# M111A.net
KiCad netlist of a schematic drawn in EAGLE
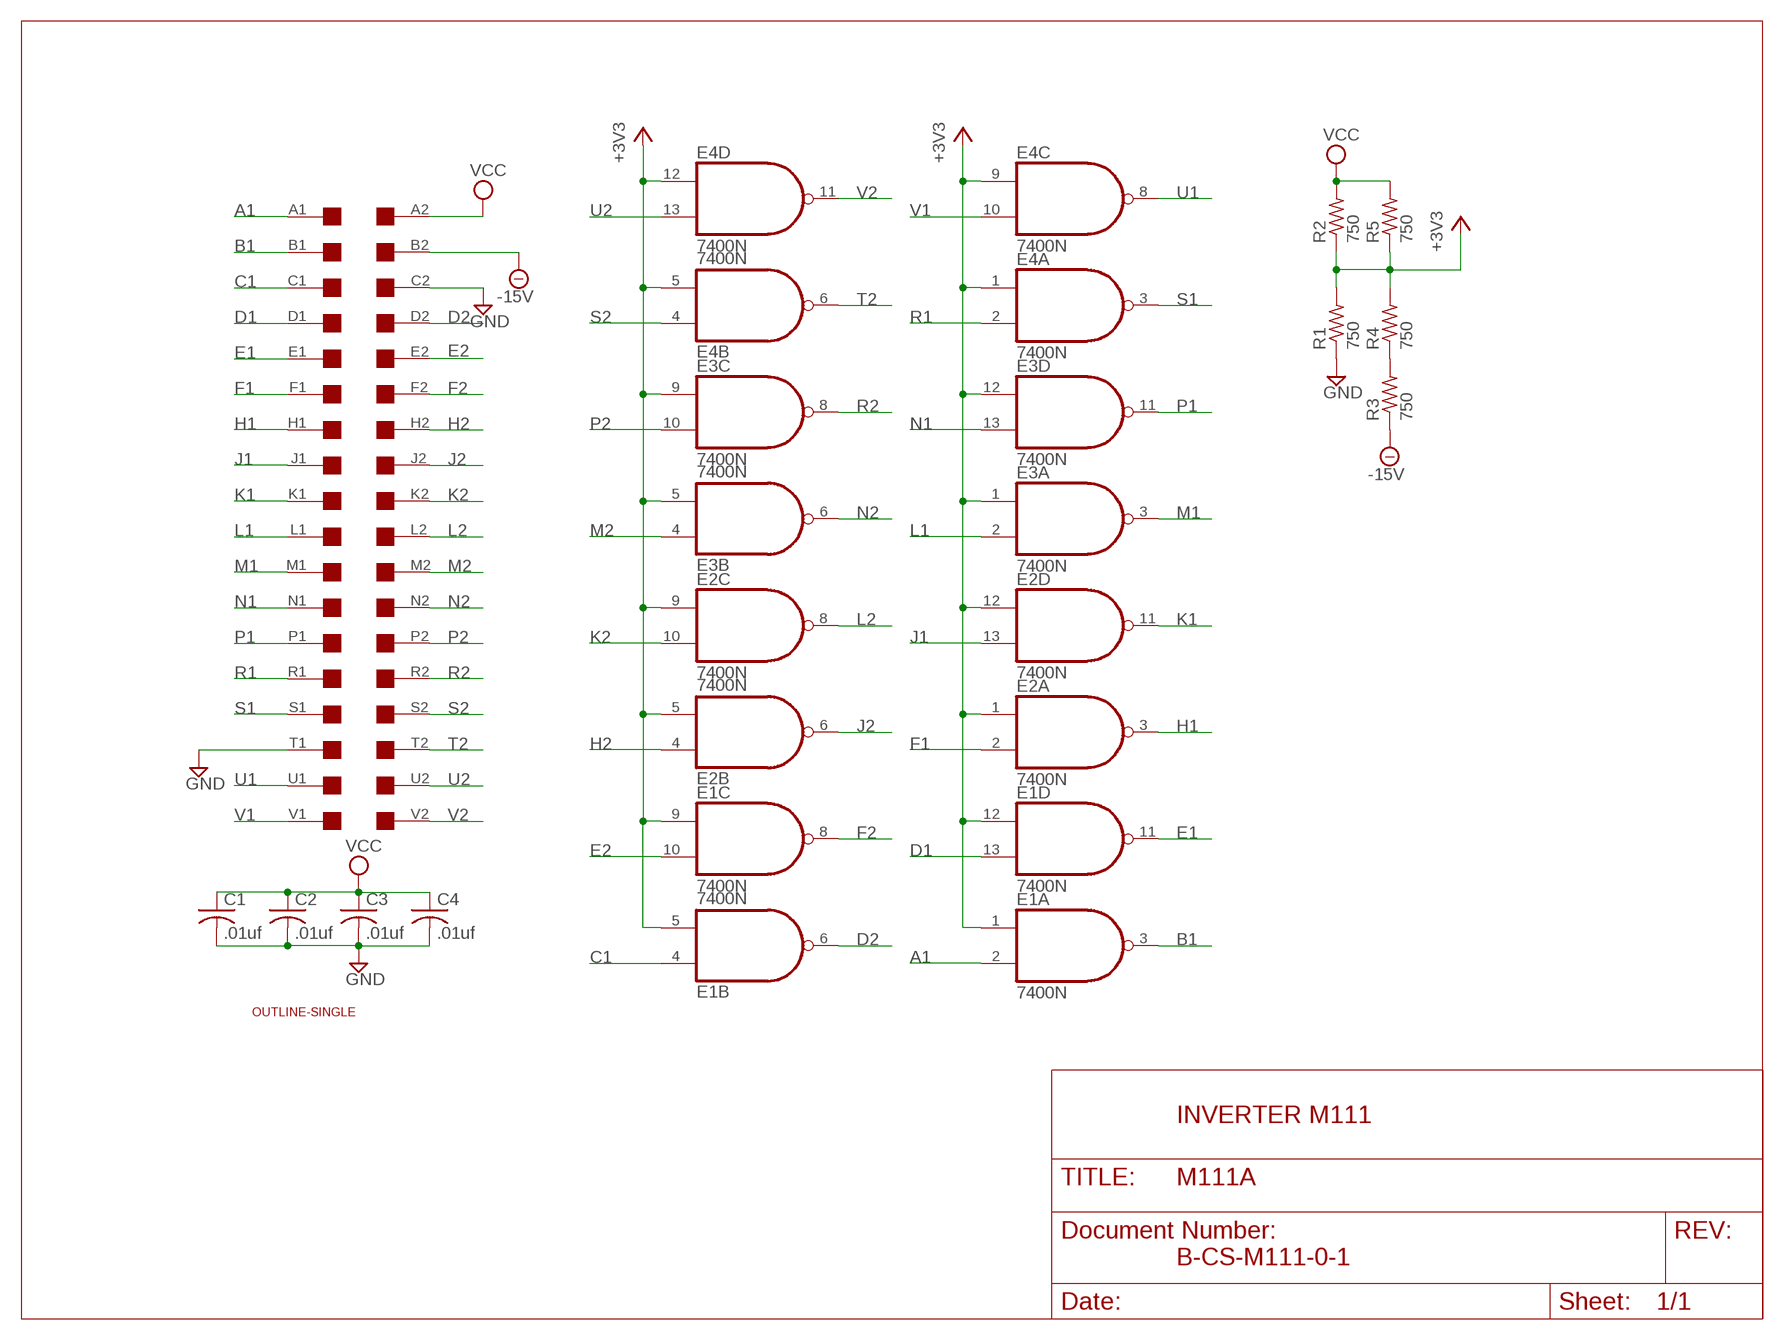
[diagram p0: schematic, sheet 1]

(export (version "E")
  (design (tool "Eeschema 10.0.6"))
  (components
    (comp (ref "A")
      (value "EDGE-2CONNECTOR")
      (footprint "eagle-import:EDGE-CON2")
      (libsource (lib "eagle-import") (part "EDGE-2CONNECTOR"))
    )
    (comp (ref "C1")
      (value ".01uf")
      (footprint "eagle-import:C050-025X075")
      (libsource (lib "eagle-import") (part "C-US050-025X075"))
    )
    (comp (ref "C2")
      (value ".01uf")
      (footprint "eagle-import:C050-025X075")
      (libsource (lib "eagle-import") (part "C-US050-025X075"))
    )
    (comp (ref "C3")
      (value ".01uf")
      (footprint "eagle-import:C050-025X075")
      (libsource (lib "eagle-import") (part "C-US050-025X075"))
    )
    (comp (ref "C4")
      (value ".01uf")
      (footprint "eagle-import:C050-025X075")
      (libsource (lib "eagle-import") (part "C-US050-025X075"))
    )
    (comp (ref "E1")
      (value "7400N")
      (footprint "eagle-import:DIL14")
      (libsource (lib "eagle-import") (part "7400N"))
    )
    (comp (ref "E2")
      (value "7400N")
      (footprint "eagle-import:DIL14")
      (libsource (lib "eagle-import") (part "7400N"))
    )
    (comp (ref "E3")
      (value "7400N")
      (footprint "eagle-import:DIL14")
      (libsource (lib "eagle-import") (part "7400N"))
    )
    (comp (ref "E4")
      (value "7400N")
      (footprint "eagle-import:DIL14")
      (libsource (lib "eagle-import") (part "7400N"))
    )
    (comp (ref "R1")
      (value "750")
      (footprint "eagle-import:0207_10")
      (libsource (lib "eagle-import") (part "R-US_0207/10"))
    )
    (comp (ref "R2")
      (value "750")
      (footprint "eagle-import:0207_10")
      (libsource (lib "eagle-import") (part "R-US_0207/10"))
    )
    (comp (ref "R3")
      (value "750")
      (footprint "eagle-import:0207_10")
      (libsource (lib "eagle-import") (part "R-US_0207/10"))
    )
    (comp (ref "R4")
      (value "750")
      (footprint "eagle-import:0207_10")
      (libsource (lib "eagle-import") (part "R-US_0207/10"))
    )
    (comp (ref "R5")
      (value "750")
      (footprint "eagle-import:0207_10")
      (libsource (lib "eagle-import") (part "R-US_0207/10"))
    )
    (comp (ref "U$1")
      (value "OUTLINE-SINGLE")
      (footprint "eagle-import:SINGLE")
      (libsource (lib "eagle-import") (part "OUTLINE-SINGLE"))
    )
  )
  (nets
    (net (code "1") (name "+3V3") (class "Default")
      (node (ref "E1") (pin "1") (pinfunction "I0_1") (pintype "input"))
      (node (ref "E1") (pin "12") (pinfunction "I0_12") (pintype "input"))
      (node (ref "E1") (pin "5") (pinfunction "I1_5") (pintype "input"))
      (node (ref "E1") (pin "9") (pinfunction "I0_9") (pintype "input"))
      (node (ref "E2") (pin "1") (pinfunction "I0_1") (pintype "input"))
      (node (ref "E2") (pin "12") (pinfunction "I0_12") (pintype "input"))
      (node (ref "E2") (pin "5") (pinfunction "I1_5") (pintype "input"))
      (node (ref "E2") (pin "9") (pinfunction "I0_9") (pintype "input"))
      (node (ref "E3") (pin "1") (pinfunction "I0_1") (pintype "input"))
      (node (ref "E3") (pin "12") (pinfunction "I0_12") (pintype "input"))
      (node (ref "E3") (pin "5") (pinfunction "I1_5") (pintype "input"))
      (node (ref "E3") (pin "9") (pinfunction "I0_9") (pintype "input"))
      (node (ref "E4") (pin "1") (pinfunction "I0_1") (pintype "input"))
      (node (ref "E4") (pin "12") (pinfunction "I0_12") (pintype "input"))
      (node (ref "E4") (pin "5") (pinfunction "I1_5") (pintype "input"))
      (node (ref "E4") (pin "9") (pinfunction "I0_9") (pintype "input"))
      (node (ref "R1") (pin "2") (pinfunction "2_2") (pintype "passive"))
      (node (ref "R2") (pin "1") (pinfunction "1_1") (pintype "passive"))
      (node (ref "R4") (pin "2") (pinfunction "2_2") (pintype "passive"))
      (node (ref "R5") (pin "1") (pinfunction "1_1") (pintype "passive"))
    )
    (net (code "2") (name "-15V") (class "Default")
      (node (ref "A") (pin "B2") (pinfunction "1_B2") (pintype "bidirectional"))
      (node (ref "R3") (pin "1") (pinfunction "1_1") (pintype "passive"))
    )
    (net (code "3") (name "/A1") (class "Default")
      (node (ref "A") (pin "A1") (pinfunction "1_A1") (pintype "bidirectional"))
      (node (ref "E1") (pin "2") (pinfunction "I1_2") (pintype "input"))
    )
    (net (code "4") (name "/B1") (class "Default")
      (node (ref "A") (pin "B1") (pinfunction "1_B1") (pintype "bidirectional"))
      (node (ref "E1") (pin "3") (pinfunction "O_3") (pintype "output"))
    )
    (net (code "5") (name "/C1") (class "Default")
      (node (ref "A") (pin "C1") (pinfunction "1_C1") (pintype "bidirectional"))
      (node (ref "E1") (pin "4") (pinfunction "I0_4") (pintype "input"))
    )
    (net (code "6") (name "/D1") (class "Default")
      (node (ref "A") (pin "D1") (pinfunction "1_D1") (pintype "bidirectional"))
      (node (ref "E1") (pin "13") (pinfunction "I1_13") (pintype "input"))
    )
    (net (code "7") (name "/D2") (class "Default")
      (node (ref "A") (pin "D2") (pinfunction "1_D2") (pintype "bidirectional"))
      (node (ref "E1") (pin "6") (pinfunction "O_6") (pintype "output"))
    )
    (net (code "8") (name "/E1") (class "Default")
      (node (ref "A") (pin "E1") (pinfunction "1_E1") (pintype "bidirectional"))
      (node (ref "E1") (pin "11") (pinfunction "O_11") (pintype "output"))
    )
    (net (code "9") (name "/E2") (class "Default")
      (node (ref "A") (pin "E2") (pinfunction "1_E2") (pintype "bidirectional"))
      (node (ref "E1") (pin "10") (pinfunction "I1_10") (pintype "input"))
    )
    (net (code "10") (name "/F1") (class "Default")
      (node (ref "A") (pin "F1") (pinfunction "1_F1") (pintype "bidirectional"))
      (node (ref "E2") (pin "2") (pinfunction "I1_2") (pintype "input"))
    )
    (net (code "11") (name "/F2") (class "Default")
      (node (ref "A") (pin "F2") (pinfunction "1_F2") (pintype "bidirectional"))
      (node (ref "E1") (pin "8") (pinfunction "O_8") (pintype "output"))
    )
    (net (code "12") (name "/H1") (class "Default")
      (node (ref "A") (pin "H1") (pinfunction "1_H1") (pintype "bidirectional"))
      (node (ref "E2") (pin "3") (pinfunction "O_3") (pintype "output"))
    )
    (net (code "13") (name "/H2") (class "Default")
      (node (ref "A") (pin "H2") (pinfunction "1_H2") (pintype "bidirectional"))
      (node (ref "E2") (pin "4") (pinfunction "I0_4") (pintype "input"))
    )
    (net (code "14") (name "/J1") (class "Default")
      (node (ref "A") (pin "J1") (pinfunction "1_J1") (pintype "bidirectional"))
      (node (ref "E2") (pin "13") (pinfunction "I1_13") (pintype "input"))
    )
    (net (code "15") (name "/J2") (class "Default")
      (node (ref "A") (pin "J2") (pinfunction "1_J2") (pintype "bidirectional"))
      (node (ref "E2") (pin "6") (pinfunction "O_6") (pintype "output"))
    )
    (net (code "16") (name "/K1") (class "Default")
      (node (ref "A") (pin "K1") (pinfunction "1_K1") (pintype "bidirectional"))
      (node (ref "E2") (pin "11") (pinfunction "O_11") (pintype "output"))
    )
    (net (code "17") (name "/K2") (class "Default")
      (node (ref "A") (pin "K2") (pinfunction "1_K2") (pintype "bidirectional"))
      (node (ref "E2") (pin "10") (pinfunction "I1_10") (pintype "input"))
    )
    (net (code "18") (name "/L1") (class "Default")
      (node (ref "A") (pin "L1") (pinfunction "1_L1") (pintype "bidirectional"))
      (node (ref "E3") (pin "2") (pinfunction "I1_2") (pintype "input"))
    )
    (net (code "19") (name "/L2") (class "Default")
      (node (ref "A") (pin "L2") (pinfunction "1_L2") (pintype "bidirectional"))
      (node (ref "E2") (pin "8") (pinfunction "O_8") (pintype "output"))
    )
    (net (code "20") (name "/M1") (class "Default")
      (node (ref "A") (pin "M1") (pinfunction "1_M1") (pintype "bidirectional"))
      (node (ref "E3") (pin "3") (pinfunction "O_3") (pintype "output"))
    )
    (net (code "21") (name "/M2") (class "Default")
      (node (ref "A") (pin "M2") (pinfunction "1_M2") (pintype "bidirectional"))
      (node (ref "E3") (pin "4") (pinfunction "I0_4") (pintype "input"))
    )
    (net (code "22") (name "/N1") (class "Default")
      (node (ref "A") (pin "N1") (pinfunction "1_N1") (pintype "bidirectional"))
      (node (ref "E3") (pin "13") (pinfunction "I1_13") (pintype "input"))
    )
    (net (code "23") (name "/N2") (class "Default")
      (node (ref "A") (pin "N2") (pinfunction "1_N2") (pintype "bidirectional"))
      (node (ref "E3") (pin "6") (pinfunction "O_6") (pintype "output"))
    )
    (net (code "24") (name "/P1") (class "Default")
      (node (ref "A") (pin "P1") (pinfunction "1_P1") (pintype "bidirectional"))
      (node (ref "E3") (pin "11") (pinfunction "O_11") (pintype "output"))
    )
    (net (code "25") (name "/P2") (class "Default")
      (node (ref "A") (pin "P2") (pinfunction "1_P2") (pintype "bidirectional"))
      (node (ref "E3") (pin "10") (pinfunction "I1_10") (pintype "input"))
    )
    (net (code "26") (name "/R1") (class "Default")
      (node (ref "A") (pin "R1") (pinfunction "1_R1") (pintype "bidirectional"))
      (node (ref "E4") (pin "2") (pinfunction "I1_2") (pintype "input"))
    )
    (net (code "27") (name "/R2") (class "Default")
      (node (ref "A") (pin "R2") (pinfunction "1_R2") (pintype "bidirectional"))
      (node (ref "E3") (pin "8") (pinfunction "O_8") (pintype "output"))
    )
    (net (code "28") (name "/S1") (class "Default")
      (node (ref "A") (pin "S1") (pinfunction "1_S1") (pintype "bidirectional"))
      (node (ref "E4") (pin "3") (pinfunction "O_3") (pintype "output"))
    )
    (net (code "29") (name "/S2") (class "Default")
      (node (ref "A") (pin "S2") (pinfunction "1_S2") (pintype "bidirectional"))
      (node (ref "E4") (pin "4") (pinfunction "I0_4") (pintype "input"))
    )
    (net (code "30") (name "/T2") (class "Default")
      (node (ref "A") (pin "T2") (pinfunction "1_T2") (pintype "bidirectional"))
      (node (ref "E4") (pin "6") (pinfunction "O_6") (pintype "output"))
    )
    (net (code "31") (name "/U1") (class "Default")
      (node (ref "A") (pin "U1") (pinfunction "1_U1") (pintype "bidirectional"))
      (node (ref "E4") (pin "8") (pinfunction "O_8") (pintype "output"))
    )
    (net (code "32") (name "/U2") (class "Default")
      (node (ref "A") (pin "U2") (pinfunction "1_U2") (pintype "bidirectional"))
      (node (ref "E4") (pin "13") (pinfunction "I1_13") (pintype "input"))
    )
    (net (code "33") (name "/V1") (class "Default")
      (node (ref "A") (pin "V1") (pinfunction "1_V1") (pintype "bidirectional"))
      (node (ref "E4") (pin "10") (pinfunction "I1_10") (pintype "input"))
    )
    (net (code "34") (name "/V2") (class "Default")
      (node (ref "A") (pin "V2") (pinfunction "1_V2") (pintype "bidirectional"))
      (node (ref "E4") (pin "11") (pinfunction "O_11") (pintype "output"))
    )
    (net (code "35") (name "GND") (class "Default")
      (node (ref "A") (pin "C2") (pinfunction "1_C2") (pintype "bidirectional"))
      (node (ref "A") (pin "T1") (pinfunction "1_T1") (pintype "bidirectional"))
      (node (ref "C1") (pin "2") (pinfunction "2_2") (pintype "passive"))
      (node (ref "C2") (pin "2") (pinfunction "2_2") (pintype "passive"))
      (node (ref "C3") (pin "2") (pinfunction "2_2") (pintype "passive"))
      (node (ref "C4") (pin "2") (pinfunction "2_2") (pintype "passive"))
      (node (ref "R1") (pin "1") (pinfunction "1_1") (pintype "passive"))
    )
    (net (code "36") (name "Net-(R3-Pad2)") (class "Default")
      (node (ref "R3") (pin "2") (pinfunction "2_2") (pintype "passive"))
      (node (ref "R4") (pin "1") (pinfunction "1_1") (pintype "passive"))
    )
    (net (code "37") (name "VCC") (class "Default")
      (node (ref "A") (pin "A2") (pinfunction "1_A2") (pintype "bidirectional"))
      (node (ref "C1") (pin "1") (pinfunction "1_1") (pintype "passive"))
      (node (ref "C2") (pin "1") (pinfunction "1_1") (pintype "passive"))
      (node (ref "C3") (pin "1") (pinfunction "1_1") (pintype "passive"))
      (node (ref "C4") (pin "1") (pinfunction "1_1") (pintype "passive"))
      (node (ref "R2") (pin "2") (pinfunction "2_2") (pintype "passive"))
      (node (ref "R5") (pin "2") (pinfunction "2_2") (pintype "passive"))
    )
  )
)
